# LED.net
KiCad netlist of a schematic drawn in Altium Designer
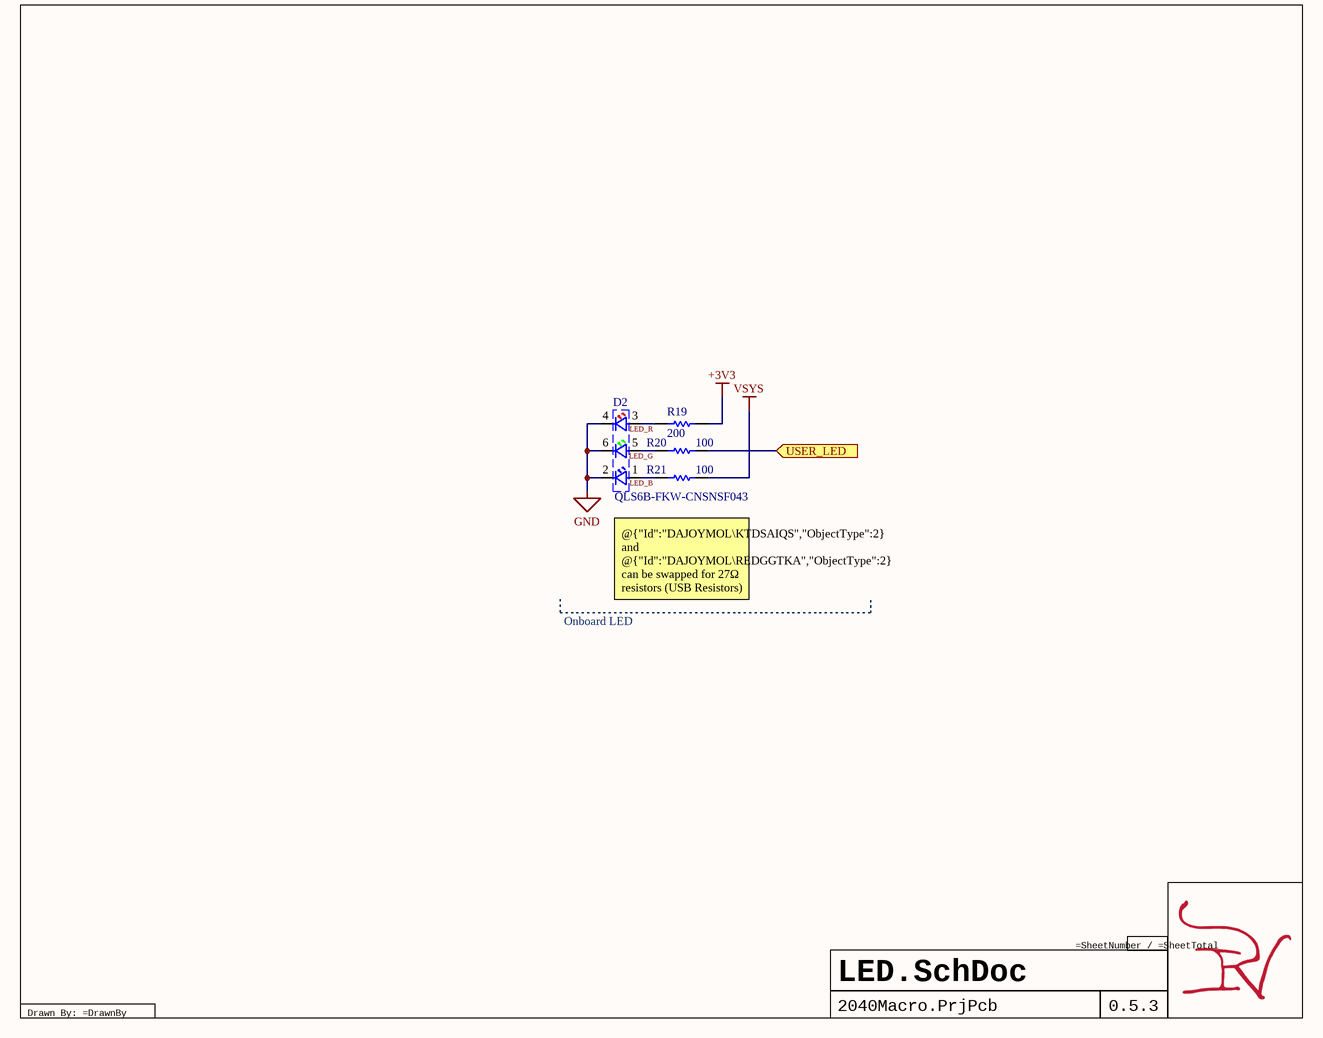
[diagram p0: LED.SchDoc]

(export (version "E")
  (design (tool "Eeschema 10.0.6"))
  (components
    (comp (ref "D2")
      (value "QLS6B-FKW-CNSNSF043")
      (footprint "LED_QLS6B-FKW-CNSNSF043")
      (description "Triple Color LED, Red/green/blue")
      (fields (field (name "MF") "{'manufacturer': u'Cree Inc.'}"))
      (libsource (lib "IIT Motorsports") (part "QLS6B-FKW-CNSNSF043"))
    )
    (comp (ref "R19")
      (value "200")
      (footprint "RES 0201_0603")
      (fields
        (field (name "POWER") "50mW")
        (field (name "TOLERANCE") "1%")
        (field (name "Comment") "200-0201-0.05/1")
      )
      (libsource (lib "IIT Motorsports") (part "RES"))
    )
    (comp (ref "R20")
      (value "100")
      (footprint "RES 0201_0603")
      (fields
        (field (name "POWER") "50mW")
        (field (name "TOLERANCE") "1%")
        (field (name "Comment") "100-0201-0.05/1")
      )
      (libsource (lib "IIT Motorsports") (part "RES"))
    )
    (comp (ref "R21")
      (value "100")
      (footprint "RES 0201_0603")
      (fields
        (field (name "POWER") "50mW")
        (field (name "TOLERANCE") "1%")
        (field (name "Comment") "100-0201-0.05/1")
      )
      (libsource (lib "IIT Motorsports") (part "RES"))
    )
  )
  (nets
    (net (code "1") (name "+3V3") (class "Default")
      (node (ref "R19") (pin "2") (pinfunction "2_2") (pintype "passive"))
    )
    (net (code "2") (name "/LED_B") (class "Default")
      (node (ref "D2") (pin "1") (pinfunction "BLUE_ANODE_1") (pintype "passive"))
      (node (ref "R21") (pin "1") (pinfunction "1_1") (pintype "passive"))
    )
    (net (code "3") (name "/LED_G") (class "Default")
      (node (ref "D2") (pin "5") (pinfunction "GREEN_ANODE_5") (pintype "passive"))
      (node (ref "R20") (pin "1") (pinfunction "1_1") (pintype "passive"))
    )
    (net (code "4") (name "/LED_R") (class "Default")
      (node (ref "D2") (pin "3") (pinfunction "RED_ANODE_3") (pintype "passive"))
      (node (ref "R19") (pin "1") (pinfunction "1_1") (pintype "passive"))
    )
    (net (code "5") (name "/USER_LED") (class "Default")
      (node (ref "R20") (pin "2") (pinfunction "2_2") (pintype "passive"))
    )
    (net (code "6") (name "GND") (class "Default")
      (node (ref "D2") (pin "2") (pinfunction "BLUE_CATHODE_2") (pintype "passive"))
      (node (ref "D2") (pin "4") (pinfunction "RED_CATHODE_4") (pintype "passive"))
      (node (ref "D2") (pin "6") (pinfunction "GREEN_CATHODE_6") (pintype "passive"))
    )
    (net (code "7") (name "VSYS") (class "Default")
      (node (ref "R21") (pin "2") (pinfunction "2_2") (pintype "passive"))
    )
  )
)
